# Schematic_sch.net
KiCad netlist of a schematic drawn in EAGLE
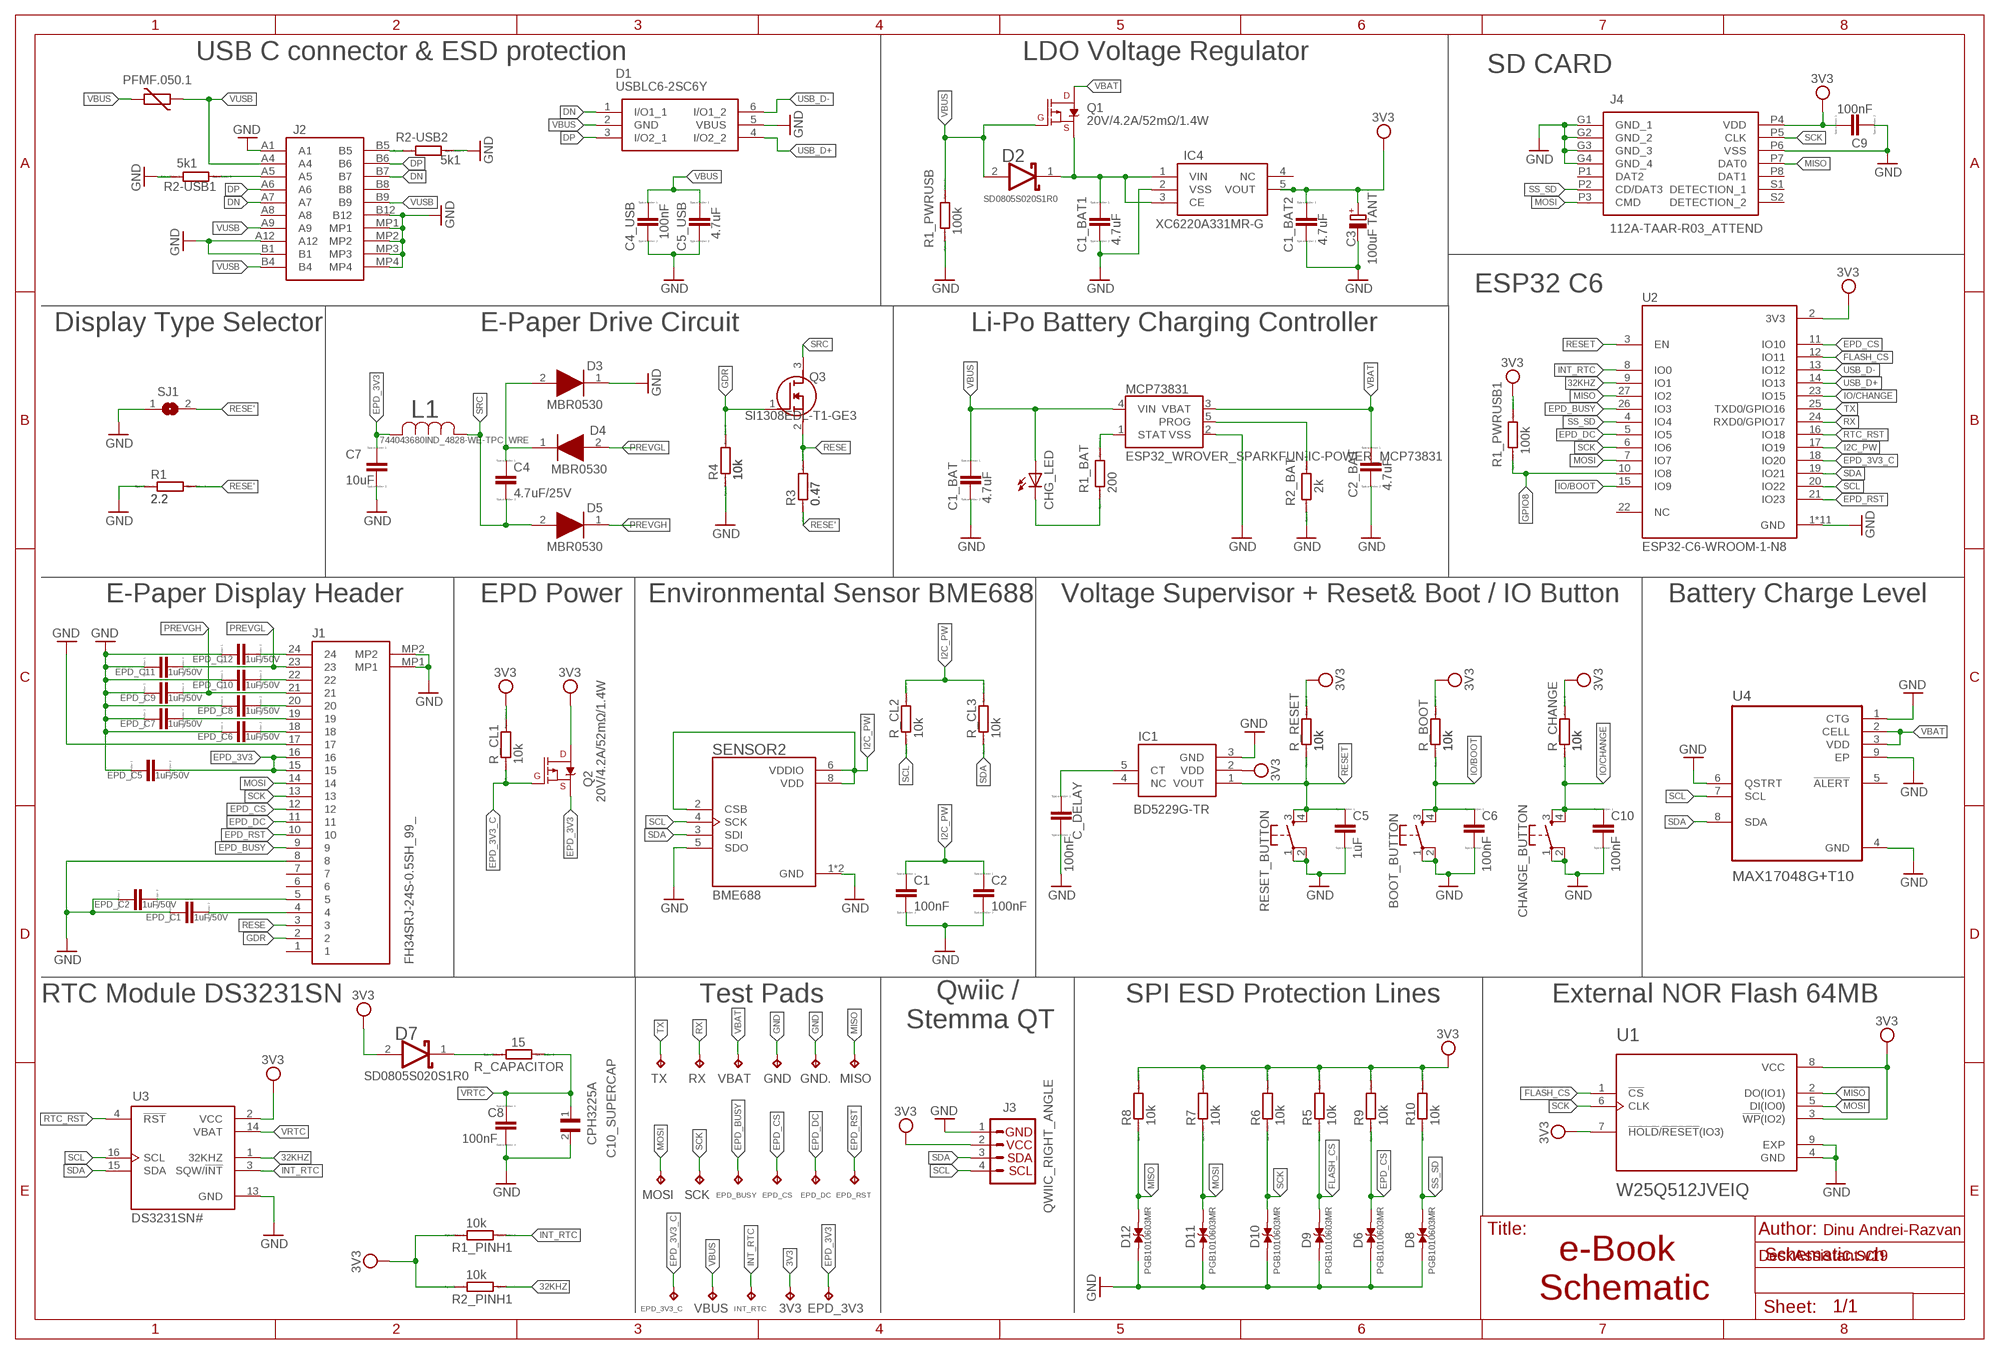
[diagram p0: schematic, sheet 1]

(export (version "E")
  (design (tool "Eeschema 10.0.6"))
  (components
    (comp (ref "3V3")
      (value "TPTP20R")
      (footprint "eagle-import:TP20R")
      (libsource (lib "eagle-import") (part "TPTP20R"))
    )
    (comp (ref "BOOT_BUTTON")
      (value "BUTTON_CUSYOMV1")
      (footprint "eagle-import:MYBUTTON")
      (libsource (lib "eagle-import") (part "BUTTON_CUSYOMV1"))
    )
    (comp (ref "C1")
      (value "100nF")
      (footprint "eagle-import:EAGLE-LTSPICE_C0402")
      (libsource (lib "eagle-import") (part "EAGLE-LTSPICE_CC0402"))
    )
    (comp (ref "C1_BAT")
      (value "4.7uF")
      (footprint "eagle-import:EAGLE-LTSPICE_C0402")
      (libsource (lib "eagle-import") (part "EAGLE-LTSPICE_CC0402"))
    )
    (comp (ref "C1_BAT1")
      (value "4.7uF")
      (footprint "eagle-import:EAGLE-LTSPICE_C0402")
      (libsource (lib "eagle-import") (part "EAGLE-LTSPICE_CC0402"))
    )
    (comp (ref "C1_BAT2")
      (value "4.7uF")
      (footprint "eagle-import:EAGLE-LTSPICE_C0402")
      (libsource (lib "eagle-import") (part "EAGLE-LTSPICE_CC0402"))
    )
    (comp (ref "C2")
      (value "100nF")
      (footprint "eagle-import:EAGLE-LTSPICE_C0402")
      (libsource (lib "eagle-import") (part "EAGLE-LTSPICE_CC0402"))
    )
    (comp (ref "C2_BAT")
      (value "4.7uF")
      (footprint "eagle-import:EAGLE-LTSPICE_C0402")
      (libsource (lib "eagle-import") (part "EAGLE-LTSPICE_CC0402"))
    )
    (comp (ref "C3")
      (value "100uF TANT")
      (footprint "eagle-import:RCL_CT3528")
      (libsource (lib "eagle-import") (part "RCL_CPOL-EUCT3528"))
    )
    (comp (ref "C4")
      (value "4.7uF/25V")
      (footprint "eagle-import:EAGLE-LTSPICE_C0402")
      (libsource (lib "eagle-import") (part "EAGLE-LTSPICE_CC0402"))
    )
    (comp (ref "C4_USB")
      (value "100nF")
      (footprint "eagle-import:ESP32_WROVER_EAGLE-LTSPICE_C0402")
      (libsource (lib "eagle-import") (part "ESP32_WROVER_EAGLE-LTSPICE_CC0402"))
    )
    (comp (ref "C5")
      (value "1uF")
      (footprint "eagle-import:EAGLE-LTSPICE_C0402")
      (libsource (lib "eagle-import") (part "EAGLE-LTSPICE_CC0402"))
    )
    (comp (ref "C5_USB")
      (value "4.7uF")
      (footprint "eagle-import:ESP32_WROVER_EAGLE-LTSPICE_C0402")
      (libsource (lib "eagle-import") (part "ESP32_WROVER_EAGLE-LTSPICE_CC0402"))
    )
    (comp (ref "C6")
      (value "100nF")
      (footprint "eagle-import:EAGLE-LTSPICE_C0402")
      (libsource (lib "eagle-import") (part "EAGLE-LTSPICE_CC0402"))
    )
    (comp (ref "C7")
      (value "10uF")
      (footprint "eagle-import:EAGLE-LTSPICE_C0402")
      (libsource (lib "eagle-import") (part "EAGLE-LTSPICE_CC0402"))
    )
    (comp (ref "C8")
      (value "100nF")
      (footprint "eagle-import:EAGLE-LTSPICE_C0402")
      (libsource (lib "eagle-import") (part "EAGLE-LTSPICE_CC0402"))
    )
    (comp (ref "C9")
      (value "100nF")
      (footprint "eagle-import:ESP32_WROVER_EAGLE-LTSPICE_C0402")
      (libsource (lib "eagle-import") (part "ESP32_WROVER_EAGLE-LTSPICE_CC0402"))
    )
    (comp (ref "C10")
      (value "100nF")
      (footprint "eagle-import:EAGLE-LTSPICE_C0402")
      (libsource (lib "eagle-import") (part "EAGLE-LTSPICE_CC0402"))
    )
    (comp (ref "C10_SUPERCAP")
      (value "CPH3225A")
      (footprint "eagle-import:CAPCP3225X100N")
      (fields (field (name "MF") "Seiko Instruments"))
      (libsource (lib "eagle-import") (part "CPH3225A"))
    )
    (comp (ref "CHANGE_BUTTON")
      (value "BUTTON_CUSYOMV1")
      (footprint "eagle-import:MYBUTTON")
      (libsource (lib "eagle-import") (part "BUTTON_CUSYOMV1"))
    )
    (comp (ref "CHG_LED")
      (value "ADAFRUIT_LEDCHIP-LED0603")
      (footprint "eagle-import:ADAFRUIT_CHIP-LED0603")
      (libsource (lib "eagle-import") (part "ADAFRUIT_LEDCHIP-LED0603"))
    )
    (comp (ref "C_DELAY")
      (value "100nF")
      (footprint "eagle-import:EAGLE-LTSPICE_C0402")
      (libsource (lib "eagle-import") (part "EAGLE-LTSPICE_CC0402"))
    )
    (comp (ref "D1")
      (value "USBLC6-2SC6Y")
      (footprint "eagle-import:SOT95P280X145-6N")
      (fields (field (name "MF") "STMicroelectronics"))
      (libsource (lib "eagle-import") (part "USBLC6-2SC6Y"))
    )
    (comp (ref "D2")
      (value "ESP32_WROVER_AVX---SD0805S020S1R0_AVX_SD0805S020S1R0_0_0AVX_SD0805S020S1R0_0_0")
      (footprint "eagle-import:ESP32_WROVER_AVX---SD0805S020S1R0_AVX_SD0805S020S1R0_0")
      (fields
        (field (name "DIGIKEY_PART_NUMBER") "478-7800-1-ND")
        (field (name "MF") "AVX")
        (field (name "MOUSER_PART_NUMBER") "581-SD0805S020S1R0")
      )
      (libsource (lib "eagle-import") (part "ESP32_WROVER_AVX---SD0805S020S1R0_AVX_SD0805S020S1R0_0_0AVX_SD0805S020S1R0_0_0"))
    )
    (comp (ref "D3")
      (value "MBR0530")
      (footprint "eagle-import:SOD3716X135N")
      (fields (field (name "MF") "ON Semiconductor"))
      (libsource (lib "eagle-import") (part "MBR0530"))
    )
    (comp (ref "D4")
      (value "MBR0530")
      (footprint "eagle-import:SOD3716X135N")
      (fields (field (name "MF") "ON Semiconductor"))
      (libsource (lib "eagle-import") (part "MBR0530"))
    )
    (comp (ref "D5")
      (value "MBR0530")
      (footprint "eagle-import:SOD3716X135N")
      (fields (field (name "MF") "ON Semiconductor"))
      (libsource (lib "eagle-import") (part "MBR0530"))
    )
    (comp (ref "D6")
      (value "PGB1010603MR")
      (footprint "eagle-import:DIOC1608X36N")
      (fields (field (name "MF") "Littelfuse Inc."))
      (libsource (lib "eagle-import") (part "PGB1010603MR"))
    )
    (comp (ref "D7")
      (value "ESP32_WROVER_AVX---SD0805S020S1R0_AVX_SD0805S020S1R0_0_0AVX_SD0805S020S1R0_0_0")
      (footprint "eagle-import:ESP32_WROVER_AVX---SD0805S020S1R0_AVX_SD0805S020S1R0_0")
      (fields
        (field (name "DIGIKEY_PART_NUMBER") "478-7800-1-ND")
        (field (name "MF") "AVX")
        (field (name "MOUSER_PART_NUMBER") "581-SD0805S020S1R0")
      )
      (libsource (lib "eagle-import") (part "ESP32_WROVER_AVX---SD0805S020S1R0_AVX_SD0805S020S1R0_0_0AVX_SD0805S020S1R0_0_0"))
    )
    (comp (ref "D8")
      (value "PGB1010603MR")
      (footprint "eagle-import:DIOC1608X36N")
      (fields (field (name "MF") "Littelfuse Inc."))
      (libsource (lib "eagle-import") (part "PGB1010603MR"))
    )
    (comp (ref "D9")
      (value "PGB1010603MR")
      (footprint "eagle-import:DIOC1608X36N")
      (fields (field (name "MF") "Littelfuse Inc."))
      (libsource (lib "eagle-import") (part "PGB1010603MR"))
    )
    (comp (ref "D10")
      (value "PGB1010603MR")
      (footprint "eagle-import:DIOC1608X36N")
      (fields (field (name "MF") "Littelfuse Inc."))
      (libsource (lib "eagle-import") (part "PGB1010603MR"))
    )
    (comp (ref "D11")
      (value "PGB1010603MR")
      (footprint "eagle-import:DIOC1608X36N")
      (fields (field (name "MF") "Littelfuse Inc."))
      (libsource (lib "eagle-import") (part "PGB1010603MR"))
    )
    (comp (ref "D12")
      (value "PGB1010603MR")
      (footprint "eagle-import:DIOC1608X36N")
      (fields (field (name "MF") "Littelfuse Inc."))
      (libsource (lib "eagle-import") (part "PGB1010603MR"))
    )
    (comp (ref "EPD_3V3")
      (value "TPTP20R")
      (footprint "eagle-import:TP20R")
      (libsource (lib "eagle-import") (part "TPTP20R"))
    )
    (comp (ref "EPD_3V3_C")
      (value "TPTP20R")
      (footprint "eagle-import:TP20R")
      (libsource (lib "eagle-import") (part "TPTP20R"))
    )
    (comp (ref "EPD_BUSY")
      (value "TPTP20R")
      (footprint "eagle-import:TP20R")
      (libsource (lib "eagle-import") (part "TPTP20R"))
    )
    (comp (ref "EPD_C1")
      (value "1uF/50V")
      (footprint "eagle-import:EAGLE-LTSPICE_C0402")
      (libsource (lib "eagle-import") (part "EAGLE-LTSPICE_CC0402"))
    )
    (comp (ref "EPD_C2")
      (value "1uF/50V")
      (footprint "eagle-import:EAGLE-LTSPICE_C0402")
      (libsource (lib "eagle-import") (part "EAGLE-LTSPICE_CC0402"))
    )
    (comp (ref "EPD_C5")
      (value "1uF/50V")
      (footprint "eagle-import:EAGLE-LTSPICE_C0402")
      (libsource (lib "eagle-import") (part "EAGLE-LTSPICE_CC0402"))
    )
    (comp (ref "EPD_C6")
      (value "1uF/50V")
      (footprint "eagle-import:EAGLE-LTSPICE_C0402")
      (libsource (lib "eagle-import") (part "EAGLE-LTSPICE_CC0402"))
    )
    (comp (ref "EPD_C7")
      (value "1uF/50V")
      (footprint "eagle-import:EAGLE-LTSPICE_C0402")
      (libsource (lib "eagle-import") (part "EAGLE-LTSPICE_CC0402"))
    )
    (comp (ref "EPD_C8")
      (value "1uF/50V")
      (footprint "eagle-import:EAGLE-LTSPICE_C0402")
      (libsource (lib "eagle-import") (part "EAGLE-LTSPICE_CC0402"))
    )
    (comp (ref "EPD_C9")
      (value "1uF/50V")
      (footprint "eagle-import:EAGLE-LTSPICE_C0402")
      (libsource (lib "eagle-import") (part "EAGLE-LTSPICE_CC0402"))
    )
    (comp (ref "EPD_C10")
      (value "1uF/50V")
      (footprint "eagle-import:EAGLE-LTSPICE_C0402")
      (libsource (lib "eagle-import") (part "EAGLE-LTSPICE_CC0402"))
    )
    (comp (ref "EPD_C11")
      (value "1uF/50V")
      (footprint "eagle-import:EAGLE-LTSPICE_C0402")
      (libsource (lib "eagle-import") (part "EAGLE-LTSPICE_CC0402"))
    )
    (comp (ref "EPD_C12")
      (value "1uF/50V")
      (footprint "eagle-import:EAGLE-LTSPICE_C0402")
      (libsource (lib "eagle-import") (part "EAGLE-LTSPICE_CC0402"))
    )
    (comp (ref "EPD_CS")
      (value "TPTP20R")
      (footprint "eagle-import:TP20R")
      (libsource (lib "eagle-import") (part "TPTP20R"))
    )
    (comp (ref "EPD_DC")
      (value "TPTP20R")
      (footprint "eagle-import:TP20R")
      (libsource (lib "eagle-import") (part "TPTP20R"))
    )
    (comp (ref "EPD_RST")
      (value "TPTP20R")
      (footprint "eagle-import:TP20R")
      (libsource (lib "eagle-import") (part "TPTP20R"))
    )
    (comp (ref "GND")
      (value "TPTP20R")
      (footprint "eagle-import:TP20R")
      (libsource (lib "eagle-import") (part "TPTP20R"))
    )
    (comp (ref "GND.")
      (value "TPTP20R")
      (footprint "eagle-import:TP20R")
      (libsource (lib "eagle-import") (part "TPTP20R"))
    )
    (comp (ref "IC1")
      (value "BD5229G-TR")
      (footprint "eagle-import:SOT95P280X125-5N")
      (fields (field (name "MOUSER_PART_NUMBER") "755-BD5229G-TR"))
      (libsource (lib "eagle-import") (part "BD5229G-TR"))
    )
    (comp (ref "IC4")
      (value "XC6220A331MR-G")
      (footprint "eagle-import:SOT95P280X120-5N")
      (fields (field (name "MOUSER_PART_NUMBER") "865-XC6220A331MR-G"))
      (libsource (lib "eagle-import") (part "XC6220A331MR-G"))
    )
    (comp (ref "INT_RTC")
      (value "TPTP20R")
      (footprint "eagle-import:TP20R")
      (libsource (lib "eagle-import") (part "TPTP20R"))
    )
    (comp (ref "J1")
      (value "FH34SRJ-24S-0.5SH_99_")
      (footprint "eagle-import:FH34SRJ24S05SH99")
      (fields
        (field (name "MANUFACTURER_PART_NUMBER") "FH34SRJ-24S-0.5SH(99)")
        (field (name "MOUSER_PART_NUMBER") "798-FH34SRJ24S05SH99")
      )
      (libsource (lib "eagle-import") (part "FH34SRJ-24S-0.5SH_99_"))
    )
    (comp (ref "J2")
      (value "SAMACSYS_PARTS_USB4110-GF-A")
      (footprint "eagle-import:SAMACSYS_PARTS_USB4110GFA")
      (fields
        (field (name "MANUFACTURER_PART_NUMBER") "USB4110-GF-A")
        (field (name "MOUSER_PART_NUMBER") "640-USB4110-GF-A")
      )
      (libsource (lib "eagle-import") (part "SAMACSYS_PARTS_USB4110-GF-A"))
    )
    (comp (ref "J3")
      (value "QWIIC_RIGHT_ANGLE")
      (footprint "eagle-import:JST04_1MM_RA")
      (libsource (lib "eagle-import") (part "QWIIC_CONNECTORJS-1MM"))
    )
    (comp (ref "J4")
      (value "112A-TAAR-R03_ATTEND")
      (footprint "eagle-import:112ATAARR03ATTEND")
      (fields (field (name "MANUFACTURER_PART_NUMBER") "112A-TAAR-R03 ATTEND"))
      (libsource (lib "eagle-import") (part "112A-TAAR-R03_ATTEND"))
    )
    (comp (ref "L1")
      (value "744043680IND_4828-WE-TPC_WRE")
      (footprint "eagle-import:IND_4828-WE-TPC_WRE")
      (fields
        (field (name "MANUFACTURER_PART_NUMBER") "744043680")
        (field (name "COPYRIGHT") "Copyright (C) 2024 Ultra Librarian. All rights reserved.")
      )
      (libsource (lib "eagle-import") (part "744043680IND_4828-WE-TPC_WRE"))
    )
    (comp (ref "MCP73831")
      (value "ESP32_WROVER_SPARKFUN-IC-POWER_MCP73831")
      (footprint "eagle-import:ESP32_WROVER_SPARKFUN-IC-POWER_SOT23-5")
      (libsource (lib "eagle-import") (part "ESP32_WROVER_SPARKFUN-IC-POWER_MCP73831"))
    )
    (comp (ref "MISO")
      (value "TPTP20R")
      (footprint "eagle-import:TP20R")
      (libsource (lib "eagle-import") (part "TPTP20R"))
    )
    (comp (ref "MOSI")
      (value "TPTP20R")
      (footprint "eagle-import:TP20R")
      (libsource (lib "eagle-import") (part "TPTP20R"))
    )
    (comp (ref "PFMF.050.1")
      (value "ESP32C6_VARISTORCN1812")
      (footprint "eagle-import:ESP32C6_VARISTOR_CT_CN1812")
      (libsource (lib "eagle-import") (part "ESP32C6_VARISTORCN1812"))
    )
    (comp (ref "Q1")
      (value "20V/4.2A/52mΩ/1.4W")
      (footprint "eagle-import:ESP32_WROVER_SPARKFUN-DISCRETESEMI_SOT23-3")
      (libsource (lib "eagle-import") (part "ESP32_WROVER_SPARKFUN-DISCRETESEMI_MOSFET_PCH-DMG2305UX-7"))
    )
    (comp (ref "Q2")
      (value "20V/4.2A/52mΩ/1.4W")
      (footprint "eagle-import:ESP32_WROVER_SPARKFUN-DISCRETESEMI_SOT23-3")
      (libsource (lib "eagle-import") (part "ESP32_WROVER_SPARKFUN-DISCRETESEMI_MOSFET_PCH-DMG2305UX-7"))
    )
    (comp (ref "Q3")
      (value "SI1308EDL-T1-GE3")
      (footprint "eagle-import:SOT65P210X110-3N")
      (fields (field (name "MF") "Vishay Siliconix"))
      (libsource (lib "eagle-import") (part "SI1308EDL-T1-GE3"))
    )
    (comp (ref "R1")
      (value "2.2")
      (footprint "eagle-import:ESP32_WROVER_EAGLE-LTSPICE_R0402")
      (libsource (lib "eagle-import") (part "ESP32_WROVER_EAGLE-LTSPICE_RR0402"))
    )
    (comp (ref "R1_BAT")
      (value "200")
      (footprint "eagle-import:ESP32_WROVER_EAGLE-LTSPICE_R0402")
      (libsource (lib "eagle-import") (part "ESP32_WROVER_EAGLE-LTSPICE_RR0402"))
    )
    (comp (ref "R1_PINH1")
      (value "10k")
      (footprint "eagle-import:ESP32_WROVER_EAGLE-LTSPICE_R0402")
      (libsource (lib "eagle-import") (part "ESP32_WROVER_EAGLE-LTSPICE_RR0402"))
    )
    (comp (ref "R1_PWRUSB")
      (value "100k")
      (footprint "eagle-import:ESP32_WROVER_EAGLE-LTSPICE_R0402")
      (libsource (lib "eagle-import") (part "ESP32_WROVER_EAGLE-LTSPICE_RR0402"))
    )
    (comp (ref "R1_PWRUSB1")
      (value "100k")
      (footprint "eagle-import:ESP32_WROVER_EAGLE-LTSPICE_R0402")
      (libsource (lib "eagle-import") (part "ESP32_WROVER_EAGLE-LTSPICE_RR0402"))
    )
    (comp (ref "R2-USB1")
      (value "5k1")
      (footprint "eagle-import:ESP32_WROVER_EAGLE-LTSPICE_R0402")
      (libsource (lib "eagle-import") (part "ESP32_WROVER_EAGLE-LTSPICE_RR0402"))
    )
    (comp (ref "R2-USB2")
      (value "5k1")
      (footprint "eagle-import:ESP32_WROVER_EAGLE-LTSPICE_R0402")
      (libsource (lib "eagle-import") (part "ESP32_WROVER_EAGLE-LTSPICE_RR0402"))
    )
    (comp (ref "R2_BAT")
      (value "2k")
      (footprint "eagle-import:ESP32_WROVER_EAGLE-LTSPICE_R0402")
      (libsource (lib "eagle-import") (part "ESP32_WROVER_EAGLE-LTSPICE_RR0402"))
    )
    (comp (ref "R2_PINH1")
      (value "10k")
      (footprint "eagle-import:ESP32_WROVER_EAGLE-LTSPICE_R0402")
      (libsource (lib "eagle-import") (part "ESP32_WROVER_EAGLE-LTSPICE_RR0402"))
    )
    (comp (ref "R3")
      (value "0.47")
      (footprint "eagle-import:ESP32_WROVER_EAGLE-LTSPICE_R0402")
      (libsource (lib "eagle-import") (part "ESP32_WROVER_EAGLE-LTSPICE_RR0402"))
    )
    (comp (ref "R4")
      (value "10k")
      (footprint "eagle-import:ESP32_WROVER_EAGLE-LTSPICE_R0402")
      (libsource (lib "eagle-import") (part "ESP32_WROVER_EAGLE-LTSPICE_RR0402"))
    )
    (comp (ref "R5")
      (value "10k")
      (footprint "eagle-import:ESP32_WROVER_EAGLE-LTSPICE_R0402")
      (libsource (lib "eagle-import") (part "ESP32_WROVER_EAGLE-LTSPICE_RR0402"))
    )
    (comp (ref "R6")
      (value "10k")
      (footprint "eagle-import:ESP32_WROVER_EAGLE-LTSPICE_R0402")
      (libsource (lib "eagle-import") (part "ESP32_WROVER_EAGLE-LTSPICE_RR0402"))
    )
    (comp (ref "R7")
      (value "10k")
      (footprint "eagle-import:ESP32_WROVER_EAGLE-LTSPICE_R0402")
      (libsource (lib "eagle-import") (part "ESP32_WROVER_EAGLE-LTSPICE_RR0402"))
    )
    (comp (ref "R8")
      (value "10k")
      (footprint "eagle-import:ESP32_WROVER_EAGLE-LTSPICE_R0402")
      (libsource (lib "eagle-import") (part "ESP32_WROVER_EAGLE-LTSPICE_RR0402"))
    )
    (comp (ref "R9")
      (value "10k")
      (footprint "eagle-import:ESP32_WROVER_EAGLE-LTSPICE_R0402")
      (libsource (lib "eagle-import") (part "ESP32_WROVER_EAGLE-LTSPICE_RR0402"))
    )
    (comp (ref "R10")
      (value "10k")
      (footprint "eagle-import:ESP32_WROVER_EAGLE-LTSPICE_R0402")
      (libsource (lib "eagle-import") (part "ESP32_WROVER_EAGLE-LTSPICE_RR0402"))
    )
    (comp (ref "RESET_BUTTON")
      (value "BUTTON_CUSYOMV1")
      (footprint "eagle-import:MYBUTTON")
      (libsource (lib "eagle-import") (part "BUTTON_CUSYOMV1"))
    )
    (comp (ref "RX")
      (value "TPTP20R")
      (footprint "eagle-import:TP20R")
      (libsource (lib "eagle-import") (part "TPTP20R"))
    )
    (comp (ref "R_BOOT")
      (value "10k")
      (footprint "eagle-import:ESP32_WROVER_EAGLE-LTSPICE_R0402")
      (libsource (lib "eagle-import") (part "ESP32_WROVER_EAGLE-LTSPICE_RR0402"))
    )
    (comp (ref "R_CAPACITOR")
      (value "15")
      (footprint "eagle-import:ESP32_WROVER_EAGLE-LTSPICE_R0402")
      (libsource (lib "eagle-import") (part "ESP32_WROVER_EAGLE-LTSPICE_RR0402"))
    )
    (comp (ref "R_CHANGE")
      (value "10k")
      (footprint "eagle-import:ESP32_WROVER_EAGLE-LTSPICE_R0402")
      (libsource (lib "eagle-import") (part "ESP32_WROVER_EAGLE-LTSPICE_RR0402"))
    )
    (comp (ref "R_CL1")
      (value "10k")
      (footprint "eagle-import:ESP32_WROVER_EAGLE-LTSPICE_R0402")
      (libsource (lib "eagle-import") (part "ESP32_WROVER_EAGLE-LTSPICE_RR0402"))
    )
    (comp (ref "R_CL2")
      (value "10k")
      (footprint "eagle-import:ESP32_WROVER_EAGLE-LTSPICE_R0402")
      (libsource (lib "eagle-import") (part "ESP32_WROVER_EAGLE-LTSPICE_RR0402"))
    )
    (comp (ref "R_CL3")
      (value "10k")
      (footprint "eagle-import:ESP32_WROVER_EAGLE-LTSPICE_R0402")
      (libsource (lib "eagle-import") (part "ESP32_WROVER_EAGLE-LTSPICE_RR0402"))
    )
    (comp (ref "R_RESET")
      (value "10k")
      (footprint "eagle-import:ESP32_WROVER_EAGLE-LTSPICE_R0402")
      (libsource (lib "eagle-import") (part "ESP32_WROVER_EAGLE-LTSPICE_RR0402"))
    )
    (comp (ref "SCK")
      (value "TPTP20R")
      (footprint "eagle-import:TP20R")
      (libsource (lib "eagle-import") (part "TPTP20R"))
    )
    (comp (ref "SENSOR2")
      (value "ESP32_WROVER_BME680_BME680")
      (footprint "eagle-import:ESP32_WROVER_BME680_PSON80P300X300X100-8N")
      (fields (field (name "MF") "Bosch Sensortec") (field (name "MP") "BME680"))
      (libsource (lib "eagle-import") (part "ESP32_WROVER_BME680_BME680"))
    )
    (comp (ref "SJ1") (value "SJ") (footprint "eagle-import:SJ") (libsource (lib "eagle-import") (part "SJ")))
    (comp (ref "TX")
      (value "TPTP20R")
      (footprint "eagle-import:TP20R")
      (libsource (lib "eagle-import") (part "TPTP20R"))
    )
    (comp (ref "U1")
      (value "W25Q512JVEIQ")
      (footprint "eagle-import:SON127P600X800X80-9N")
      (fields (field (name "MF") "Winbond Electronics"))
      (libsource (lib "eagle-import") (part "W25Q512JVEIQ"))
    )
    (comp (ref "U2")
      (value "ESP32-C6-WROOM-1-N8")
      (footprint "eagle-import:XCVR_ESP32-C6-WROOM-1-N8")
      (fields (field (name "MF") "Espressif Systems"))
      (libsource (lib "eagle-import") (part "ESP32-C6-WROOM-1-N8"))
    )
    (comp (ref "U3")
      (value "DS3231SN#")
      (footprint "eagle-import:SOIC127P1032X265-16N")
      (fields (field (name "MF") "Analog Devices"))
      (libsource (lib "eagle-import") (part "DS3231SN#"))
    )
    (comp (ref "U4")
      (value "MAX17048G+T10")
      (footprint "eagle-import:SON50P200X200X80-9N")
      (fields (field (name "MF") "Analog Devices"))
      (libsource (lib "eagle-import") (part "MAX17048G+T10"))
    )
    (comp (ref "VBAT")
      (value "TPTP20R")
      (footprint "eagle-import:TP20R")
      (libsource (lib "eagle-import") (part "TPTP20R"))
    )
    (comp (ref "VBUS")
      (value "TPTP20R")
      (footprint "eagle-import:TP20R")
      (libsource (lib "eagle-import") (part "TPTP20R"))
    )
  )
  (nets
    (net (code "1") (name "3V3") (class "Default")
      (node (ref "3V3") (pin "TP") (pinfunction "TP_TP") (pintype "input"))
      (node (ref "C1_BAT2") (pin "1") (pinfunction "1_1") (pintype "passive"))
      (node (ref "C3") (pin "+") (pinfunction "+_+") (pintype "passive"))
      (node (ref "C9") (pin "1") (pinfunction "1_1") (pintype "passive"))
      (node (ref "D7") (pin "2") (pinfunction "ANODE_2") (pintype "bidirectional"))
      (node (ref "IC1") (pin "2") (pinfunction "VDD_2") (pintype "bidirectional"))
      (node (ref "IC4") (pin "5") (pinfunction "VOUT_5") (pintype "bidirectional"))
      (node (ref "J3") (pin "2") (pinfunction "2_2") (pintype "power_in"))
      (node (ref "J4") (pin "P4") (pinfunction "VDD_P4") (pintype "bidirectional"))
      (node (ref "Q2") (pin "3") (pinfunction "D_3") (pintype "bidirectional"))
      (node (ref "R10") (pin "2") (pinfunction "2_2") (pintype "passive"))
      (node (ref "R1_PINH1") (pin "2") (pinfunction "2_2") (pintype "passive"))
      (node (ref "R1_PWRUSB1") (pin "2") (pinfunction "2_2") (pintype "passive"))
      (node (ref "R2_PINH1") (pin "2") (pinfunction "2_2") (pintype "passive"))
      (node (ref "R5") (pin "2") (pinfunction "2_2") (pintype "passive"))
      (node (ref "R6") (pin "2") (pinfunction "2_2") (pintype "passive"))
      (node (ref "R7") (pin "2") (pinfunction "2_2") (pintype "passive"))
      (node (ref "R8") (pin "2") (pinfunction "2_2") (pintype "passive"))
      (node (ref "R9") (pin "2") (pinfunction "2_2") (pintype "passive"))
      (node (ref "R_BOOT") (pin "2") (pinfunction "2_2") (pintype "passive"))
      (node (ref "R_CHANGE") (pin "2") (pinfunction "2_2") (pintype "passive"))
      (node (ref "R_CL1") (pin "2") (pinfunction "2_2") (pintype "passive"))
      (node (ref "R_RESET") (pin "2") (pinfunction "2_2") (pintype "passive"))
      (node (ref "U1") (pin "3") (pinfunction "~{WP}(IO2)_3") (pintype "bidirectional"))
      (node (ref "U1") (pin "7") (pinfunction "~{HOLD}/~{RESET}(IO3)_7") (pintype "bidirectional"))
      (node (ref "U1") (pin "8") (pinfunction "VCC_8") (pintype "power_in"))
      (node (ref "U2") (pin "2") (pinfunction "3V3_2") (pintype "power_in"))
      (node (ref "U3") (pin "2") (pinfunction "VCC_2") (pintype "power_in"))
    )
    (net (code "2") (name "32KHZ") (class "Default")
      (node (ref "R2_PINH1") (pin "1") (pinfunction "1_1") (pintype "passive"))
      (node (ref "U2") (pin "9") (pinfunction "IO1_9") (pintype "bidirectional"))
      (node (ref "U3") (pin "1") (pinfunction "32KHZ_1") (pintype "output"))
    )
    (net (code "3") (name "DN") (class "Default")
      (node (ref "D1") (pin "1") (pinfunction "I/O1_1_1") (pintype "bidirectional"))
      (node (ref "J2") (pin "A7") (pinfunction "A7_A7") (pintype "bidirectional"))
      (node (ref "J2") (pin "B7") (pinfunction "B7_B7") (pintype "bidirectional"))
    )
    (net (code "4") (name "DP") (class "Default")
      (node (ref "D1") (pin "3") (pinfunction "I/O2_1_3") (pintype "bidirectional"))
      (node (ref "J2") (pin "A6") (pinfunction "A6_A6") (pintype "bidirectional"))
      (node (ref "J2") (pin "B6") (pinfunction "B6_B6") (pintype "bidirectional"))
    )
    (net (code "5") (name "EPD_3V3") (class "Default")
      (node (ref "C7") (pin "1") (pinfunction "1_1") (pintype "passive"))
      (node (ref "EPD_3V3") (pin "TP") (pinfunction "TP_TP") (pintype "input"))
      (node (ref "EPD_C5") (pin "2") (pinfunction "2_2") (pintype "passive"))
      (node (ref "J1") (pin "15") (pinfunction "15_15") (pintype "bidirectional"))
      (node (ref "J1") (pin "16") (pinfunction "16_16") (pintype "bidirectional"))
      (node (ref "L1") (pin "2") (pinfunction "2_2") (pintype "passive"))
      (node (ref "Q2") (pin "2") (pinfunction "S_2") (pintype "bidirectional"))
    )
    (net (code "6") (name "EPD_3V3_C") (class "Default")
      (node (ref "EPD_3V3_C") (pin "TP") (pinfunction "TP_TP") (pintype "input"))
      (node (ref "Q2") (pin "1") (pinfunction "G_1") (pintype "bidirectional"))
      (node (ref "R_CL1") (pin "1") (pinfunction "1_1") (pintype "passive"))
      (node (ref "U2") (pin "18") (pinfunction "IO20_18") (pintype "bidirectional"))
    )
    (net (code "7") (name "EPD_BUSY") (class "Default")
      (node (ref "EPD_BUSY") (pin "TP") (pinfunction "TP_TP") (pintype "input"))
      (node (ref "J1") (pin "9") (pinfunction "9_9") (pintype "bidirectional"))
      (node (ref "U2") (pin "26") (pinfunction "IO3_26") (pintype "bidirectional"))
    )
    (net (code "8") (name "EPD_CS") (class "Default")
      (node (ref "D6") (pin "2") (pinfunction "2_2") (pintype "passive"))
      (node (ref "EPD_CS") (pin "TP") (pinfunction "TP_TP") (pintype "input"))
      (node (ref "J1") (pin "12") (pinfunction "12_12") (pintype "bidirectional"))
      (node (ref "R9") (pin "1") (pinfunction "1_1") (pintype "passive"))
      (node (ref "U2") (pin "11") (pinfunction "IO10_11") (pintype "bidirectional"))
    )
    (net (code "9") (name "EPD_DC") (class "Default")
      (node (ref "EPD_DC") (pin "TP") (pinfunction "TP_TP") (pintype "input"))
      (node (ref "J1") (pin "11") (pinfunction "11_11") (pintype "bidirectional"))
      (node (ref "U2") (pin "5") (pinfunction "IO5_5") (pintype "bidirectional"))
    )
    (net (code "10") (name "EPD_RST") (class "Default")
      (node (ref "EPD_RST") (pin "TP") (pinfunction "TP_TP") (pintype "input"))
      (node (ref "J1") (pin "10") (pinfunction "10_10") (pintype "bidirectional"))
      (node (ref "U2") (pin "21") (pinfunction "IO23_21") (pintype "bidirectional"))
    )
    (net (code "11") (name "FLASH_CS") (class "Default")
      (node (ref "D9") (pin "2") (pinfunction "2_2") (pintype "passive"))
      (node (ref "R5") (pin "1") (pinfunction "1_1") (pintype "passive"))
      (node (ref "U1") (pin "1") (pinfunction "~{CS}_1") (pintype "input"))
      (node (ref "U2") (pin "12") (pinfunction "IO11_12") (pintype "bidirectional"))
    )
    (net (code "12") (name "GDR") (class "Default")
      (node (ref "J1") (pin "2") (pinfunction "2_2") (pintype "bidirectional"))
      (node (ref "Q3") (pin "1") (pinfunction "G_1") (pintype "bidirectional"))
      (node (ref "R4") (pin "2") (pinfunction "2_2") (pintype "passive"))
    )
    (net (code "13") (name "GND") (class "Default")
      (node (ref "BOOT_BUTTON") (pin "1") (pinfunction "1_1") (pintype "passive"))
      (node (ref "BOOT_BUTTON") (pin "2") (pinfunction "2_2") (pintype "passive"))
      (node (ref "C1") (pin "2") (pinfunction "2_2") (pintype "passive"))
      (node (ref "C10") (pin "2") (pinfunction "2_2") (pintype "passive"))
      (node (ref "C10_SUPERCAP") (pin "2") (pinfunction "2_2") (pintype "passive"))
      (node (ref "C1_BAT") (pin "2") (pinfunction "2_2") (pintype "passive"))
      (node (ref "C1_BAT1") (pin "2") (pinfunction "2_2") (pintype "passive"))
      (node (ref "C1_BAT2") (pin "2") (pinfunction "2_2") (pintype "passive"))
      (node (ref "C2") (pin "2") (pinfunction "2_2") (pintype "passive"))
      (node (ref "C2_BAT") (pin "2") (pinfunction "2_2") (pintype "passive"))
      (node (ref "C3") (pin "-") (pinfunction "-_-") (pintype "passive"))
      (node (ref "C4_USB") (pin "2") (pinfunction "2_2") (pintype "passive"))
      (node (ref "C5") (pin "2") (pinfunction "2_2") (pintype "passive"))
      (node (ref "C5_USB") (pin "2") (pinfunction "2_2") (pintype "passive"))
      (node (ref "C6") (pin "2") (pinfunction "2_2") (pintype "passive"))
      (node (ref "C7") (pin "2") (pinfunction "2_2") (pintype "passive"))
      (node (ref "C8") (pin "2") (pinfunction "2_2") (pintype "passive"))
      (node (ref "C9") (pin "2") (pinfunction "2_2") (pintype "passive"))
      (node (ref "CHANGE_BUTTON") (pin "1") (pinfunction "1_1") (pintype "passive"))
      (node (ref "CHANGE_BUTTON") (pin "2") (pinfunction "2_2") (pintype "passive"))
      (node (ref "C_DELAY") (pin "2") (pinfunction "2_2") (pintype "passive"))
      (node (ref "D1") (pin "5") (pinfunction "VBUS_5") (pintype "bidirectional"))
      (node (ref "D10") (pin "1") (pinfunction "1_1") (pintype "passive"))
      (node (ref "D11") (pin "1") (pinfunction "1_1") (pintype "passive"))
      (node (ref "D12") (pin "1") (pinfunction "1_1") (pintype "passive"))
      (node (ref "D3") (pin "1") (pinfunction "K_1") (pintype "bidirectional"))
      (node (ref "D6") (pin "1") (pinfunction "1_1") (pintype "passive"))
      (node (ref "D8") (pin "1") (pinfunction "1_1") (pintype "passive"))
      (node (ref "D9") (pin "1") (pinfunction "1_1") (pintype "passive"))
      (node (ref "EPD_C1") (pin "1") (pinfunction "1_1") (pintype "passive"))
      (node (ref "EPD_C10") (pin "1") (pinfunction "1_1") (pintype "passive"))
      (node (ref "EPD_C11") (pin "1") (pinfunction "1_1") (pintype "passive"))
      (node (ref "EPD_C12") (pin "1") (pinfunction "1_1") (pintype "passive"))
      (node (ref "EPD_C2") (pin "1") (pinfunction "1_1") (pintype "passive"))
      (node (ref "EPD_C5") (pin "1") (pinfunction "1_1") (pintype "passive"))
      (node (ref "EPD_C6") (pin "1") (pinfunction "1_1") (pintype "passive"))
      (node (ref "EPD_C7") (pin "1") (pinfunction "1_1") (pintype "passive"))
      (node (ref "EPD_C8") (pin "1") (pinfunction "1_1") (pintype "passive"))
      (node (ref "EPD_C9") (pin "1") (pinfunction "1_1") (pintype "passive"))
      (node (ref "GND") (pin "TP") (pinfunction "TP_TP") (pintype "input"))
      (node (ref "GND.") (pin "TP") (pinfunction "TP_TP") (pintype "input"))
      (node (ref "IC1") (pin "3") (pinfunction "GND_3") (pintype "bidirectional"))
      (node (ref "IC4") (pin "2") (pinfunction "VSS_2") (pintype "bidirectional"))
      (node (ref "J1") (pin "17") (pinfunction "17_17") (pintype "bidirectional"))
      (node (ref "J1") (pin "8") (pinfunction "8_8") (pintype "bidirectional"))
      (node (ref "J1") (pin "MP1") (pinfunction "MP1_MP1") (pintype "bidirectional"))
      (node (ref "J1") (pin "MP2") (pinfunction "MP2_MP2") (pintype "bidirectional"))
      (node (ref "J2") (pin "A1") (pinfunction "A1_A1") (pintype "bidirectional"))
      (node (ref "J2") (pin "A12") (pinfunction "A12_A12") (pintype "bidirectional"))
      (node (ref "J2") (pin "B1") (pinfunction "B1_B1") (pintype "bidirectional"))
      (node (ref "J2") (pin "B12") (pinfunction "B12_B12") (pintype "bidirectional"))
      (node (ref "J2") (pin "MP1") (pinfunction "MP1_MP1") (pintype "bidirectional"))
      (node (ref "J2") (pin "MP2") (pinfunction "MP2_MP2") (pintype "bidirectional"))
      (node (ref "J2") (pin "MP3") (pinfunction "MP3_MP3") (pintype "bidirectional"))
      (node (ref "J2") (pin "MP4") (pinfunction "MP4_MP4") (pintype "bidirectional"))
      (node (ref "J3") (pin "1") (pinfunction "1_1") (pintype "power_in"))
      (node (ref "J4") (pin "G1") (pinfunction "GND_1_G1") (pintype "bidirectional"))
      (node (ref "J4") (pin "G2") (pinfunction "GND_2_G2") (pintype "bidirectional"))
      (node (ref "J4") (pin "G3") (pinfunction "GND_3_G3") (pintype "bidirectional"))
      (node (ref "J4") (pin "G4") (pinfunction "GND_4_G4") (pintype "bidirectional"))
      (node (ref "J4") (pin "P6") (pinfunction "VSS_P6") (pintype "bidirectional"))
      (node (ref "MCP73831") (pin "2") (pinfunction "VSS_2") (pintype "power_in"))
      (node (ref "R1") (pin "1") (pinfunction "1_1") (pintype "passive"))
      (node (ref "R1_PWRUSB") (pin "1") (pinfunction "1_1") (pintype "passive"))
      (node (ref "R2-USB1") (pin "1") (pinfunction "1_1") (pintype "passive"))
      (node (ref "R2-USB2") (pin "1") (pinfunction "1_1") (pintype "passive"))
      (node (ref "R2_BAT") (pin "1") (pinfunction "1_1") (pintype "passive"))
      (node (ref "R4") (pin "1") (pinfunction "1_1") (pintype "passive"))
      (node (ref "RESET_BUTTON") (pin "1") (pinfunction "1_1") (pintype "passive"))
      (node (ref "RESET_BUTTON") (pin "2") (pinfunction "2_2") (pintype "passive"))
      (node (ref "SENSOR2") (pin "1") (pinfunction "GND_1") (pintype "power_in"))
      (node (ref "SENSOR2") (pin "5") (pinfunction "SDO_5") (pintype "bidirectional"))
      (node (ref "SENSOR2") (pin "7") (pinfunction "GND_7") (pintype "power_in"))
      (node (ref "SJ1") (pin "1") (pinfunction "1_1") (pintype "passive"))
      (node (ref "U1") (pin "4") (pinfunction "GND_4") (pintype "power_in"))
      (node (ref "U1") (pin "9") (pinfunction "EXP_9") (pintype "passive"))
      (node (ref "U2") (pin "1") (pinfunction "GND_1") (pintype "power_in"))
      (node (ref "U2") (pin "28") (pinfunction "GND_28") (pintype "power_in"))
      (node (ref "U2") (pin "29_1") (pinfunction "GND_29_1") (pintype "power_in"))
      (node (ref "U2") (pin "29_2") (pinfunction "GND_29_2") (pintype "power_in"))
      (node (ref "U2") (pin "29_3") (pinfunction "GND_29_3") (pintype "power_in"))
      (node (ref "U2") (pin "29_4") (pinfunction "GND_29_4") (pintype "power_in"))
      (node (ref "U2") (pin "29_5") (pinfunction "GND_29_5") (pintype "power_in"))
      (node (ref "U2") (pin "29_6") (pinfunction "GND_29_6") (pintype "power_in"))
      (node (ref "U2") (pin "29_7") (pinfunction "GND_29_7") (pintype "power_in"))
      (node (ref "U2") (pin "29_8") (pinfunction "GND_29_8") (pintype "power_in"))
      (node (ref "U2") (pin "29_9") (pinfunction "GND_29_9") (pintype "power_in"))
      (node (ref "U3") (pin "13") (pinfunction "GND_13") (pintype "power_in"))
      (node (ref "U4") (pin "1") (pinfunction "CTG_1") (pintype "power_in"))
      (node (ref "U4") (pin "4") (pinfunction "GND_4") (pintype "power_in"))
      (node (ref "U4") (pin "6") (pinfunction "QSTRT_6") (pintype "input"))
      (node (ref "U4") (pin "9") (pinfunction "EP_9") (pintype "power_in"))
    )
    (net (code "14") (name "GPIO8") (class "Default")
      (node (ref "R1_PWRUSB1") (pin "1") (pinfunction "1_1") (pintype "passive"))
      (node (ref "U2") (pin "10") (pinfunction "IO8_10") (pintype "bidirectional"))
    )
    (net (code "15") (name "I2C_PW") (class "Default")
      (node (ref "C1") (pin "1") (pinfunction "1_1") (pintype "passive"))
      (node (ref "C2") (pin "1") (pinfunction "1_1") (pintype "passive"))
      (node (ref "R_CL2") (pin "2") (pinfunction "2_2") (pintype "passive"))
      (node (ref "R_CL3") (pin "2") (pinfunction "2_2") (pintype "passive"))
      (node (ref "SENSOR2") (pin "2") (pinfunction "CSB_2") (pintype "input"))
      (node (ref "SENSOR2") (pin "6") (pinfunction "VDDIO_6") (pintype "power_in"))
      (node (ref "SENSOR2") (pin "8") (pinfunction "VDD_8") (pintype "power_in"))
      (node (ref "U2") (pin "17") (pinfunction "IO19_17") (pintype "bidirectional"))
    )
    (net (code "16") (name "INT_RTC") (class "Default")
      (node (ref "INT_RTC") (pin "TP") (pinfunction "TP_TP") (pintype "input"))
      (node (ref "R1_PINH1") (pin "1") (pinfunction "1_1") (pintype "passive"))
      (node (ref "U2") (pin "8") (pinfunction "IO0_8") (pintype "bidirectional"))
      (node (ref "U3") (pin "3") (pinfunction "SQW/~{INT}_3") (pintype "output"))
    )
    (net (code "17") (name "IO{slash}BOOT") (class "Default")
      (node (ref "BOOT_BUTTON") (pin "3") (pinfunction "3_3") (pintype "passive"))
      (node (ref "BOOT_BUTTON") (pin "4") (pinfunction "4_4") (pintype "passive"))
      (node (ref "C6") (pin "1") (pinfunction "1_1") (pintype "passive"))
      (node (ref "R_BOOT") (pin "1") (pinfunction "1_1") (pintype "passive"))
      (node (ref "U2") (pin "15") (pinfunction "IO9_15") (pintype "bidirectional"))
    )
    (net (code "18") (name "IO{slash}CHANGE") (class "Default")
      (node (ref "C10") (pin "1") (pinfunction "1_1") (pintype "passive"))
      (node (ref "CHANGE_BUTTON") (pin "3") (pinfunction "3_3") (pintype "passive"))
      (node (ref "CHANGE_BUTTON") (pin "4") (pinfunction "4_4") (pintype "passive"))
      (node (ref "R_CHANGE") (pin "1") (pinfunction "1_1") (pintype "passive"))
      (node (ref "U2") (pin "23") (pinfunction "IO15_23") (pintype "bidirectional"))
    )
    (net (code "19") (name "MISO") (class "Default")
      (node (ref "D12") (pin "2") (pinfunction "2_2") (pintype "passive"))
      (node (ref "J4") (pin "P7") (pinfunction "DAT0_P7") (pintype "bidirectional"))
      (node (ref "MISO") (pin "TP") (pinfunction "TP_TP") (pintype "input"))
      (node (ref "R8") (pin "1") (pinfunction "1_1") (pintype "passive"))
      (node (ref "U1") (pin "2") (pinfunction "DO(IO1)_2") (pintype "bidirectional"))
      (node (ref "U2") (pin "27") (pinfunction "IO2_27") (pintype "bidirectional"))
    )
    (net (code "20") (name "MOSI") (class "Default")
      (node (ref "D11") (pin "2") (pinfunction "2_2") (pintype "passive"))
      (node (ref "J1") (pin "14") (pinfunction "14_14") (pintype "bidirectional"))
      (node (ref "J4") (pin "P3") (pinfunction "CMD_P3") (pintype "bidirectional"))
      (node (ref "MOSI") (pin "TP") (pinfunction "TP_TP") (pintype "input"))
      (node (ref "R7") (pin "1") (pinfunction "1_1") (pintype "passive"))
      (node (ref "U1") (pin "5") (pinfunction "DI(IO0)_5") (pintype "bidirectional"))
      (node (ref "U2") (pin "7") (pinfunction "IO7_7") (pintype "bidirectional"))
    )
    (net (code "21") (name "Net-(CHG_LED-PadC)") (class "Default")
      (node (ref "CHG_LED") (pin "C") (pinfunction "C_C") (pintype "passive"))
      (node (ref "R1_BAT") (pin "1") (pinfunction "1_1") (pintype "passive"))
    )
    (net (code "22") (name "Net-(D2-CATHODE)") (class "Default")
      (node (ref "C1_BAT1") (pin "1") (pinfunction "1_1") (pintype "passive"))
      (node (ref "D2") (pin "1") (pinfunction "CATHODE_1") (pintype "bidirectional"))
      (node (ref "IC4") (pin "1") (pinfunction "VIN_1") (pintype "bidirectional"))
      (node (ref "IC4") (pin "3") (pinfunction "CE_3") (pintype "bidirectional"))
      (node (ref "Q1") (pin "2") (pinfunction "S_2") (pintype "bidirectional"))
    )
    (net (code "23") (name "Net-(D3-A)") (class "Default")
      (node (ref "C4") (pin "1") (pinfunction "1_1") (pintype "passive"))
      (node (ref "D3") (pin "2") (pinfunction "A_2") (pintype "bidirectional"))
      (node (ref "D4") (pin "1") (pinfunction "K_1") (pintype "bidirectional"))
    )
    (net (code "24") (name "Net-(D7-CATHODE)") (class "Default")
      (node (ref "D7") (pin "1") (pinfunction "CATHODE_1") (pintype "bidirectional"))
      (node (ref "R_CAPACITOR") (pin "2") (pinfunction "2_2") (pintype "passive"))
    )
    (net (code "25") (name "Net-(EPD_C1-Pad2)") (class "Default")
      (node (ref "EPD_C1") (pin "2") (pinfunction "2_2") (pintype "passive"))
      (node (ref "J1") (pin "4") (pinfunction "4_4") (pintype "bidirectional"))
    )
    (net (code "26") (name "Net-(EPD_C2-Pad2)") (class "Default")
      (node (ref "EPD_C2") (pin "2") (pinfunction "2_2") (pintype "passive"))
      (node (ref "J1") (pin "5") (pinfunction "5_5") (pintype "bidirectional"))
    )
    (net (code "27") (name "Net-(EPD_C6-Pad2)") (class "Default")
      (node (ref "EPD_C6") (pin "2") (pinfunction "2_2") (pintype "passive"))
      (node (ref "J1") (pin "18") (pinfunction "18_18") (pintype "bidirectional"))
    )
    (net (code "28") (name "Net-(EPD_C7-Pad2)") (class "Default")
      (node (ref "EPD_C7") (pin "2") (pinfunction "2_2") (pintype "passive"))
      (node (ref "J1") (pin "19") (pinfunction "19_19") (pintype "bidirectional"))
    )
    (net (code "29") (name "Net-(EPD_C8-Pad2)") (class "Default")
      (node (ref "EPD_C8") (pin "2") (pinfunction "2_2") (pintype "passive"))
      (node (ref "J1") (pin "20") (pinfunction "20_20") (pintype "bidirectional"))
    )
    (net (code "30") (name "Net-(EPD_C10-Pad2)") (class "Default")
      (node (ref "EPD_C10") (pin "2") (pinfunction "2_2") (pintype "passive"))
      (node (ref "J1") (pin "22") (pinfunction "22_22") (pintype "bidirectional"))
    )
    (net (code "31") (name "Net-(EPD_C12-Pad2)") (class "Default")
      (node (ref "EPD_C12") (pin "2") (pinfunction "2_2") (pintype "passive"))
      (node (ref "J1") (pin "24") (pinfunction "24_24") (pintype "bidirectional"))
    )
    (net (code "32") (name "Net-(IC1-CT)") (class "Default")
      (node (ref "C_DELAY") (pin "1") (pinfunction "1_1") (pintype "passive"))
      (node (ref "IC1") (pin "5") (pinfunction "CT_5") (pintype "bidirectional"))
    )
    (net (code "33") (name "Net-(J2-PadA5)") (class "Default")
      (node (ref "J2") (pin "A5") (pinfunction "A5_A5") (pintype "bidirectional"))
      (node (ref "R2-USB1") (pin "2") (pinfunction "2_2") (pintype "passive"))
    )
    (net (code "34") (name "Net-(J2-PadB5)") (class "Default")
      (node (ref "J2") (pin "B5") (pinfunction "B5_B5") (pintype "bidirectional"))
      (node (ref "R2-USB2") (pin "2") (pinfunction "2_2") (pintype "passive"))
    )
    (net (code "35") (name "Net-(MCP73831-PROG)") (class "Default")
      (node (ref "MCP73831") (pin "5") (pinfunction "PROG_5") (pintype "input"))
      (node (ref "R2_BAT") (pin "2") (pinfunction "2_2") (pintype "passive"))
    )
    (net (code "36") (name "Net-(MCP73831-STAT)") (class "Default")
      (node (ref "MCP73831") (pin "1") (pinfunction "STAT_1") (pintype "output"))
      (node (ref "R1_BAT") (pin "2") (pinfunction "2_2") (pintype "passive"))
    )
    (net (code "37") (name "PREVGH") (class "Default")
      (node (ref "D5") (pin "1") (pinfunction "K_1") (pintype "bidirectional"))
      (node (ref "EPD_C9") (pin "2") (pinfunction "2_2") (pintype "passive"))
      (node (ref "J1") (pin "21") (pinfunction "21_21") (pintype "bidirectional"))
    )
    (net (code "38") (name "PREVGL") (class "Default")
      (node (ref "D4") (pin "2") (pinfunction "A_2") (pintype "bidirectional"))
      (node (ref "EPD_C11") (pin "2") (pinfunction "2_2") (pintype "passive"))
      (node (ref "J1") (pin "23") (pinfunction "23_23") (pintype "bidirectional"))
    )
    (net (code "39") (name "RESE") (class "Default")
      (node (ref "J1") (pin "3") (pinfunction "3_3") (pintype "bidirectional"))
      (node (ref "Q3") (pin "2") (pinfunction "S_2") (pintype "bidirectional"))
      (node (ref "R3") (pin "2") (pinfunction "2_2") (pintype "passive"))
    )
    (net (code "40") (name "RESE'") (class "Default")
      (node (ref "R1") (pin "2") (pinfunction "2_2") (pintype "passive"))
      (node (ref "R3") (pin "1") (pinfunction "1_1") (pintype "passive"))
      (node (ref "SJ1") (pin "2") (pinfunction "2_2") (pintype "passive"))
    )
    (net (code "41") (name "RESET") (class "Default")
      (node (ref "C5") (pin "1") (pinfunction "1_1") (pintype "passive"))
      (node (ref "IC1") (pin "1") (pinfunction "VOUT_1") (pintype "bidirectional"))
      (node (ref "RESET_BUTTON") (pin "3") (pinfunction "3_3") (pintype "passive"))
      (node (ref "RESET_BUTTON") (pin "4") (pinfunction "4_4") (pintype "passive"))
      (node (ref "R_RESET") (pin "1") (pinfunction "1_1") (pintype "passive"))
      (node (ref "U2") (pin "3") (pinfunction "EN_3") (pintype "input"))
    )
    (net (code "42") (name "RTC_RST") (class "Default")
      (node (ref "U2") (pin "16") (pinfunction "IO18_16") (pintype "bidirectional"))
      (node (ref "U3") (pin "4") (pinfunction "~{RST}_4") (pintype "input"))
    )
    (net (code "43") (name "RX") (class "Default")
      (node (ref "RX") (pin "TP") (pinfunction "TP_TP") (pintype "input"))
      (node (ref "U2") (pin "24") (pinfunction "RXD0/GPIO17_24") (pintype "bidirectional"))
    )
    (net (code "44") (name "SCK") (class "Default")
      (node (ref "D10") (pin "2") (pinfunction "2_2") (pintype "passive"))
      (node (ref "J1") (pin "13") (pinfunction "13_13") (pintype "bidirectional"))
      (node (ref "J4") (pin "P5") (pinfunction "CLK_P5") (pintype "bidirectional"))
      (node (ref "R6") (pin "1") (pinfunction "1_1") (pintype "passive"))
      (node (ref "SCK") (pin "TP") (pinfunction "TP_TP") (pintype "input"))
      (node (ref "U1") (pin "6") (pinfunction "CLK_6") (pintype "input"))
      (node (ref "U2") (pin "6") (pinfunction "IO6_6") (pintype "bidirectional"))
    )
    (net (code "45") (name "SCL") (class "Default")
      (node (ref "J3") (pin "4") (pinfunction "4_4") (pintype "passive"))
      (node (ref "R_CL2") (pin "1") (pinfunction "1_1") (pintype "passive"))
      (node (ref "SENSOR2") (pin "4") (pinfunction "SCK_4") (pintype "input"))
      (node (ref "U2") (pin "20") (pinfunction "IO22_20") (pintype "bidirectional"))
      (node (ref "U3") (pin "16") (pinfunction "SCL_16") (pintype "input"))
      (node (ref "U4") (pin "7") (pinfunction "SCL_7") (pintype "input"))
    )
    (net (code "46") (name "SDA") (class "Default")
      (node (ref "J3") (pin "3") (pinfunction "3_3") (pintype "passive"))
      (node (ref "R_CL3") (pin "1") (pinfunction "1_1") (pintype "passive"))
      (node (ref "SENSOR2") (pin "3") (pinfunction "SDI_3") (pintype "bidirectional"))
      (node (ref "U2") (pin "19") (pinfunction "IO21_19") (pintype "bidirectional"))
      (node (ref "U3") (pin "15") (pinfunction "SDA_15") (pintype "bidirectional"))
      (node (ref "U4") (pin "8") (pinfunction "SDA_8") (pintype "bidirectional"))
    )
    (net (code "47") (name "SRC") (class "Default")
      (node (ref "C4") (pin "2") (pinfunction "2_2") (pintype "passive"))
      (node (ref "D5") (pin "2") (pinfunction "A_2") (pintype "bidirectional"))
      (node (ref "L1") (pin "1") (pinfunction "1_1") (pintype "passive"))
      (node (ref "Q3") (pin "3") (pinfunction "D_3") (pintype "bidirectional"))
    )
    (net (code "48") (name "SS_SD") (class "Default")
      (node (ref "D8") (pin "2") (pinfunction "2_2") (pintype "passive"))
      (node (ref "J4") (pin "P2") (pinfunction "CD/DAT3_P2") (pintype "bidirectional"))
      (node (ref "R10") (pin "1") (pinfunction "1_1") (pintype "passive"))
      (node (ref "U2") (pin "4") (pinfunction "IO4_4") (pintype "bidirectional"))
    )
    (net (code "49") (name "TX") (class "Default")
      (node (ref "TX") (pin "TP") (pinfunction "TP_TP") (pintype "input"))
      (node (ref "U2") (pin "25") (pinfunction "TXD0/GPIO16_25") (pintype "bidirectional"))
    )
    (net (code "50") (name "USB_D+") (class "Default")
      (node (ref "D1") (pin "4") (pinfunction "I/O2_2_4") (pintype "bidirectional"))
      (node (ref "U2") (pin "14") (pinfunction "IO13_14") (pintype "bidirectional"))
    )
    (net (code "51") (name "USB_D-") (class "Default")
      (node (ref "D1") (pin "6") (pinfunction "I/O1_2_6") (pintype "bidirectional"))
      (node (ref "U2") (pin "13") (pinfunction "IO12_13") (pintype "bidirectional"))
    )
    (net (code "52") (name "VBAT") (class "Default")
      (node (ref "C2_BAT") (pin "1") (pinfunction "1_1") (pintype "passive"))
      (node (ref "MCP73831") (pin "3") (pinfunction "VBAT_3") (pintype "power_in"))
      (node (ref "Q1") (pin "3") (pinfunction "D_3") (pintype "bidirectional"))
      (node (ref "U4") (pin "2") (pinfunction "CELL_2") (pintype "power_in"))
      (node (ref "U4") (pin "3") (pinfunction "VDD_3") (pintype "power_in"))
      (node (ref "VBAT") (pin "TP") (pinfunction "TP_TP") (pintype "input"))
    )
    (net (code "53") (name "VBUS") (class "Default")
      (node (ref "C1_BAT") (pin "1") (pinfunction "1_1") (pintype "passive"))
      (node (ref "C4_USB") (pin "1") (pinfunction "1_1") (pintype "passive"))
      (node (ref "C5_USB") (pin "1") (pinfunction "1_1") (pintype "passive"))
      (node (ref "CHG_LED") (pin "A") (pinfunction "A_A") (pintype "passive"))
      (node (ref "D1") (pin "2") (pinfunction "GND_2") (pintype "bidirectional"))
      (node (ref "D2") (pin "2") (pinfunction "ANODE_2") (pintype "bidirectional"))
      (node (ref "MCP73831") (pin "4") (pinfunction "VIN_4") (pintype "power_in"))
      (node (ref "PFMF.050.1") (pin "2") (pinfunction "2_2") (pintype "passive"))
      (node (ref "Q1") (pin "1") (pinfunction "G_1") (pintype "bidirectional"))
      (node (ref "R1_PWRUSB") (pin "2") (pinfunction "2_2") (pintype "passive"))
      (node (ref "VBUS") (pin "TP") (pinfunction "TP_TP") (pintype "input"))
    )
    (net (code "54") (name "VRTC") (class "Default")
      (node (ref "C10_SUPERCAP") (pin "1") (pinfunction "1_1") (pintype "passive"))
      (node (ref "C8") (pin "1") (pinfunction "1_1") (pintype "passive"))
      (node (ref "R_CAPACITOR") (pin "1") (pinfunction "1_1") (pintype "passive"))
      (node (ref "U3") (pin "14") (pinfunction "VBAT_14") (pintype "power_in"))
    )
    (net (code "55") (name "VUSB") (class "Default")
      (node (ref "J2") (pin "A4") (pinfunction "A4_A4") (pintype "bidirectional"))
      (node (ref "J2") (pin "A9") (pinfunction "A9_A9") (pintype "bidirectional"))
      (node (ref "J2") (pin "B4") (pinfunction "B4_B4") (pintype "bidirectional"))
      (node (ref "J2") (pin "B9") (pinfunction "B9_B9") (pintype "bidirectional"))
      (node (ref "PFMF.050.1") (pin "1") (pinfunction "1_1") (pintype "passive"))
    )
    (net (code "56") (name "unconnected-(IC1-NC-Pad4)") (class "Default")
      (node (ref "IC1") (pin "4") (pinfunction "NC_4") (pintype "no_connect"))
    )
    (net (code "57") (name "unconnected-(IC4-NC-Pad4)") (class "Default")
      (node (ref "IC4") (pin "4") (pinfunction "NC_4") (pintype "no_connect"))
    )
    (net (code "58") (name "unconnected-(J1-Pad1)") (class "Default")
      (node (ref "J1") (pin "1") (pinfunction "1_1") (pintype "bidirectional"))
    )
    (net (code "59") (name "unconnected-(J1-Pad6)") (class "Default")
      (node (ref "J1") (pin "6") (pinfunction "6_6") (pintype "bidirectional"))
    )
    (net (code "60") (name "unconnected-(J1-Pad7)") (class "Default")
      (node (ref "J1") (pin "7") (pinfunction "7_7") (pintype "bidirectional"))
    )
    (net (code "61") (name "unconnected-(J2-PadA8)") (class "Default")
      (node (ref "J2") (pin "A8") (pinfunction "A8_A8") (pintype "bidirectional"))
    )
    (net (code "62") (name "unconnected-(J2-PadB8)") (class "Default")
      (node (ref "J2") (pin "B8") (pinfunction "B8_B8") (pintype "bidirectional"))
    )
    (net (code "63") (name "unconnected-(J4-DAT1-PadP8)") (class "Default")
      (node (ref "J4") (pin "P8") (pinfunction "DAT1_P8") (pintype "bidirectional"))
    )
    (net (code "64") (name "unconnected-(J4-DAT2-PadP1)") (class "Default")
      (node (ref "J4") (pin "P1") (pinfunction "DAT2_P1") (pintype "bidirectional"))
    )
    (net (code "65") (name "unconnected-(J4-DETECTION_1-PadS1)") (class "Default")
      (node (ref "J4") (pin "S1") (pinfunction "DETECTION_1_S1") (pintype "bidirectional"))
    )
    (net (code "66") (name "unconnected-(J4-DETECTION_2-PadS2)") (class "Default")
      (node (ref "J4") (pin "S2") (pinfunction "DETECTION_2_S2") (pintype "bidirectional"))
    )
    (net (code "67") (name "unconnected-(U2-NC-Pad22)") (class "Default")
      (node (ref "U2") (pin "22") (pinfunction "NC_22") (pintype "no_connect"))
    )
    (net (code "68") (name "unconnected-(U4-~{ALERT}-Pad5)") (class "Default")
      (node (ref "U4") (pin "5") (pinfunction "~{ALERT}_5") (pintype "output"))
    )
  )
)
